# Ethernet.net
KiCad netlist of a schematic drawn in Altium Designer
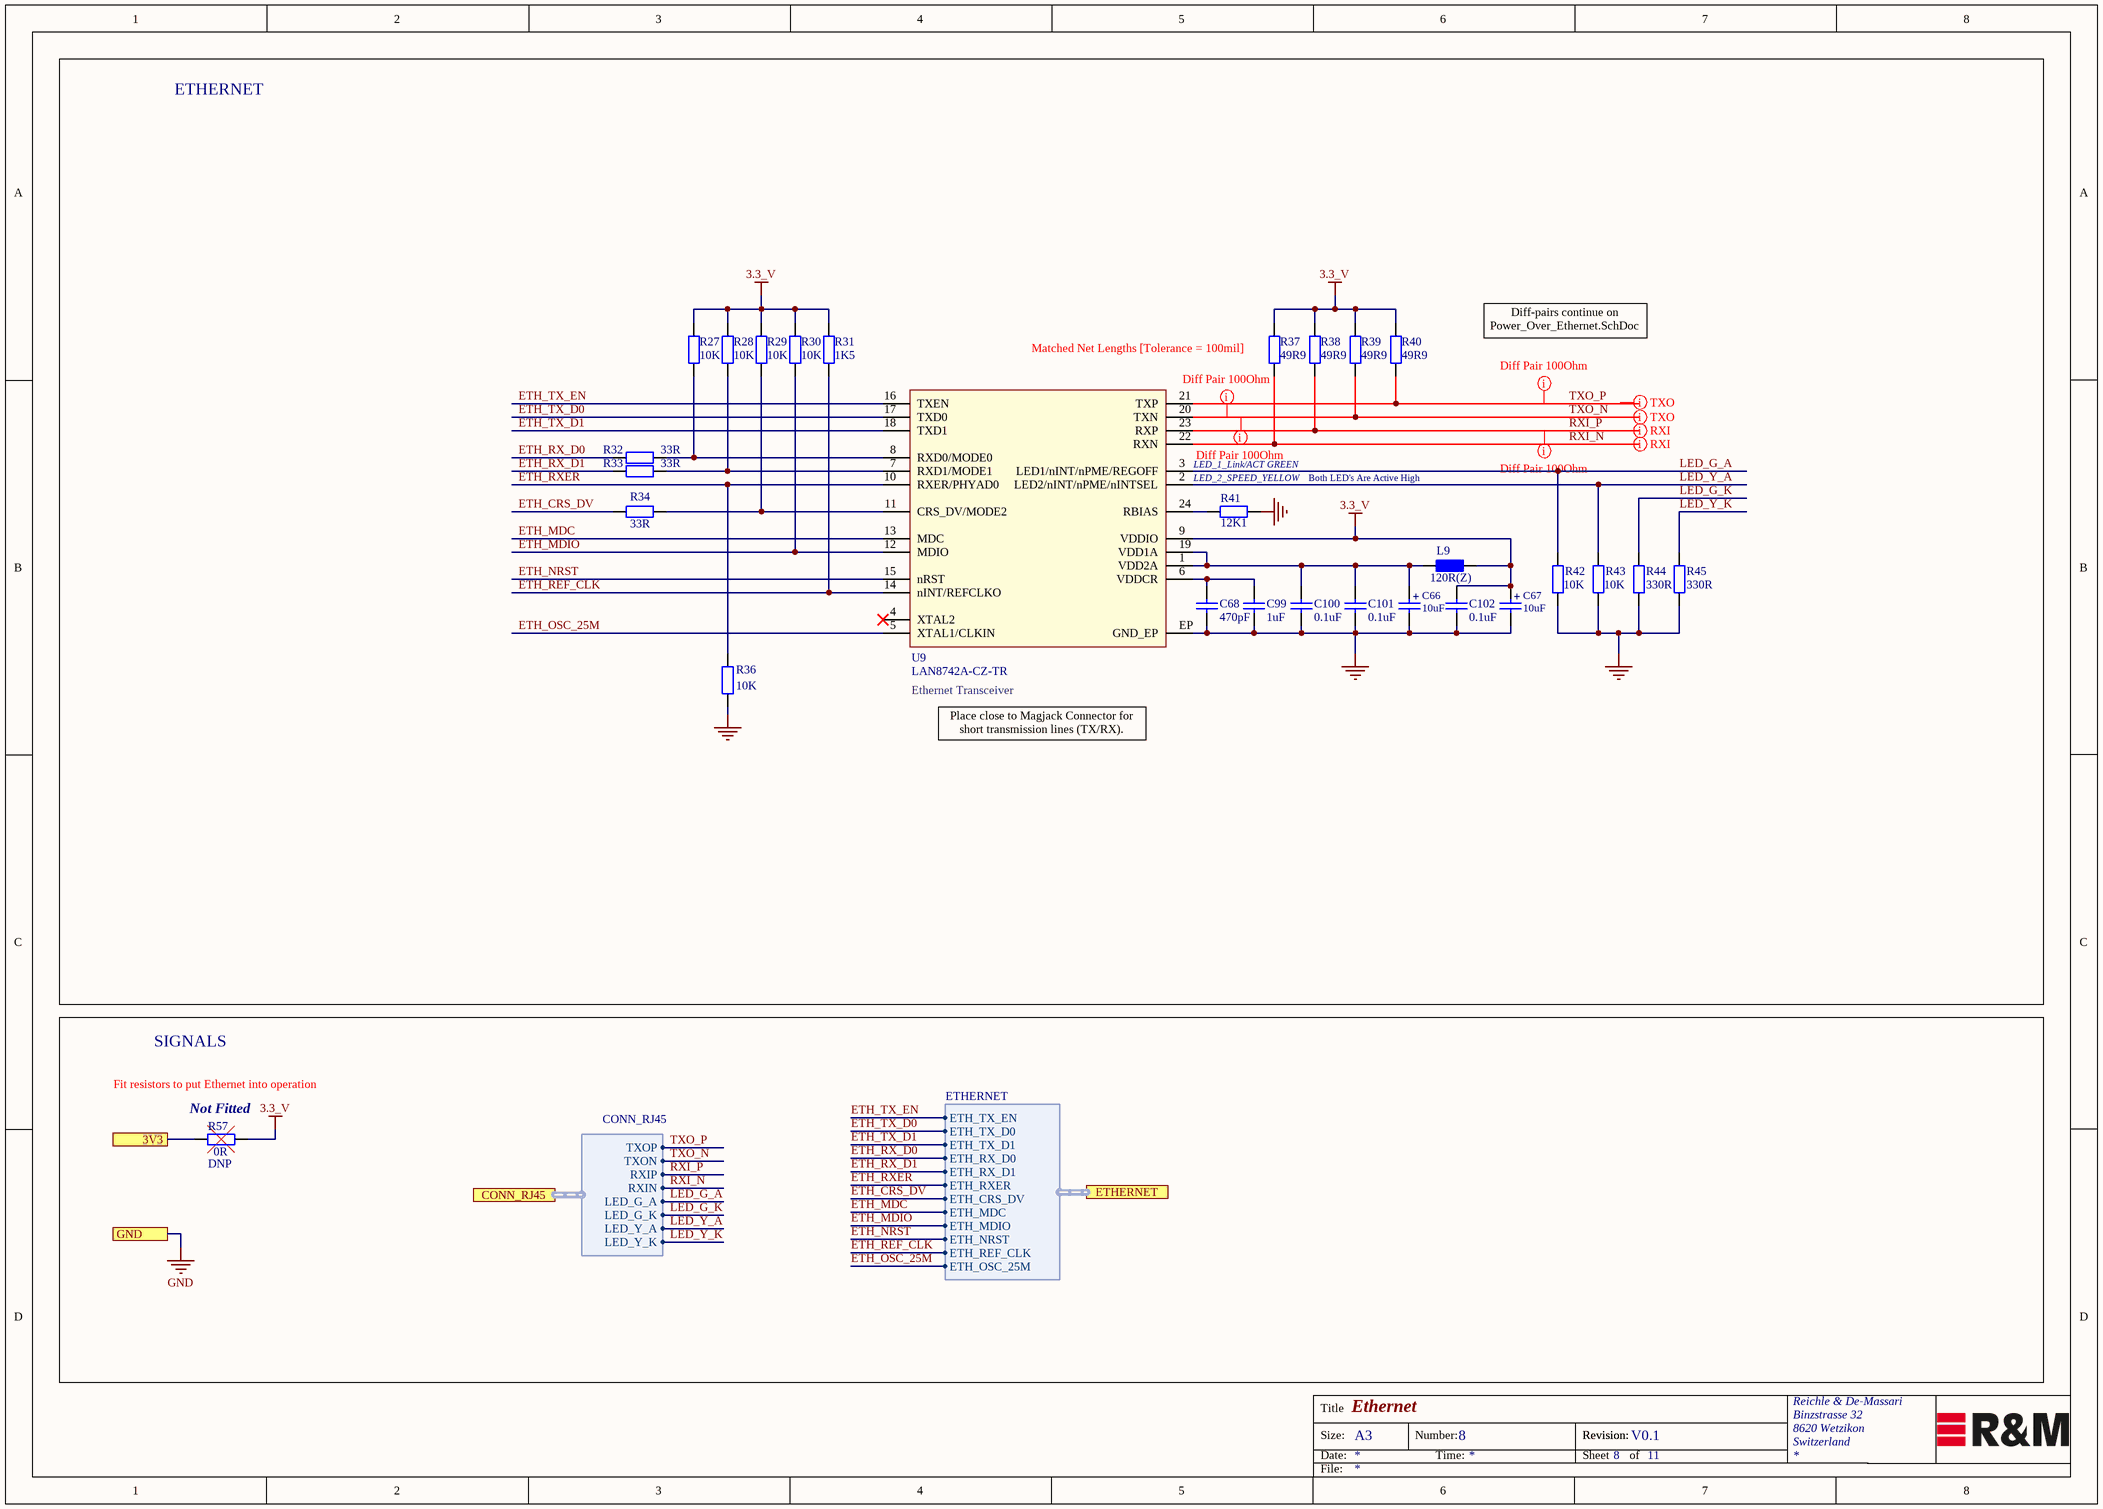
[diagram p0: Ethernet.SchDoc]

(export (version "E")
  (design (tool "Eeschema 10.0.6"))
  (components
    (comp (ref "C66")
      (value "10uF")
      (footprint "293D106X9010A2TE3")
      (description "10µF Molded Tantalum Capacitors 10V 1206 (3216 Metric) 3.4Ohm")
      (fields (field (name "MANUFACTURER") "Vishay Sprague") (field (name "VOLTAGE") "10V"))
      (libsource (lib "RDM_ALT_SCH") (part "Cap_10uF_1206 _10V_Tantal"))
    )
    (comp (ref "C67")
      (value "10uF")
      (footprint "293D106X9010A2TE3")
      (description "10µF Molded Tantalum Capacitors 10V 1206 (3216 Metric) 3.4Ohm")
      (fields (field (name "MANUFACTURER") "Vishay Sprague") (field (name "VOLTAGE") "10V"))
      (libsource (lib "RDM_ALT_SCH") (part "Cap_10uF_1206 _10V_Tantal"))
    )
    (comp (ref "C68")
      (value "470pF")
      (footprint "Ceramic Capacitor 0402 EIA")
      (description "470pF ±10% 16V Ceramic Capacitor X7R 0402 (1005 Metric)")
      (fields (field (name "TOLERANCE") "10%") (field (name "VOLTAGE") "16VDC"))
      (libsource (lib "RDM_ALT_SCH") (part "Cap_470pF_0402_16V"))
    )
    (comp (ref "C99")
      (value "1uF")
      (footprint "Ceramic Capacitor 0402 EIA")
      (description "1µF ±10% 16V Ceramic Capacitor X5R 0603 (1608 Metric)")
      (fields (field (name "TOLERANCE") "10%") (field (name "VOLTAGE") "16VDC"))
      (libsource (lib "RDM_ALT_SCH") (part "Cap_1uF_0603_16V"))
    )
    (comp (ref "C100")
      (value "0.1uF")
      (footprint "Ceramic Capacitor 0402 EIA")
      (description "0.1µF ±10% 16V Ceramic Capacitor X7R 0402 (1005 Metric)")
      (fields (field (name "TOLERANCE") "10%") (field (name "VOLTAGE") "16VDC"))
      (libsource (lib "RDM_ALT_SCH") (part "Cap_0.1uF_0402_16V_10%"))
    )
    (comp (ref "C101")
      (value "0.1uF")
      (footprint "Ceramic Capacitor 0402 EIA")
      (description "0.1µF ±10% 16V Ceramic Capacitor X7R 0402 (1005 Metric)")
      (fields (field (name "TOLERANCE") "10%") (field (name "VOLTAGE") "16VDC"))
      (libsource (lib "RDM_ALT_SCH") (part "Cap_0.1uF_0402_16V_10%"))
    )
    (comp (ref "C102")
      (value "0.1uF")
      (footprint "Ceramic Capacitor 0402 EIA")
      (description "0.1µF ±10% 16V Ceramic Capacitor X7R 0402 (1005 Metric)")
      (fields (field (name "TOLERANCE") "10%") (field (name "VOLTAGE") "16VDC"))
      (libsource (lib "RDM_ALT_SCH") (part "Cap_0.1uF_0402_16V_10%"))
    )
    (comp (ref "L9")
      (value "120R(Z)")
      (footprint "Inductor 0603 EIA")
      (description "120 Ohms @ 100MHz 1 Power Line Ferrite Bead 0603 (1608 Metric) 2A 50mOhm")
      (fields (field (name "MANUFACTURER") "Murata Electronics"))
      (libsource (lib "RDM_ALT_SCH") (part "Ferrit_Bead_0603_BLM18PG121SN1D"))
    )
    (comp (ref "R27")
      (value "10K")
      (footprint "Resistor 0402 EIA")
      (description "SMD 10K ohm 1% 50V General Purpose")
      (fields (field (name "TOLERANCE") "1%") (field (name "POWER") "63mW"))
      (libsource (lib "RDM_ALT_SCH") (part "Res_10K_0402"))
    )
    (comp (ref "R28")
      (value "10K")
      (footprint "Resistor 0402 EIA")
      (description "SMD 10K ohm 1% 50V General Purpose")
      (fields (field (name "TOLERANCE") "1%") (field (name "POWER") "63mW"))
      (libsource (lib "RDM_ALT_SCH") (part "Res_10K_0402"))
    )
    (comp (ref "R29")
      (value "10K")
      (footprint "Resistor 0402 EIA")
      (description "SMD 10K ohm 1% 50V General Purpose")
      (fields (field (name "TOLERANCE") "1%") (field (name "POWER") "63mW"))
      (libsource (lib "RDM_ALT_SCH") (part "Res_10K_0402"))
    )
    (comp (ref "R30")
      (value "10K")
      (footprint "Resistor 0402 EIA")
      (description "SMD 10K ohm 1% 50V General Purpose")
      (fields (field (name "TOLERANCE") "1%") (field (name "POWER") "63mW"))
      (libsource (lib "RDM_ALT_SCH") (part "Res_10K_0402"))
    )
    (comp (ref "R31")
      (value "1K5")
      (footprint "Resistor 0402 EIA")
      (description "1 kOhms ±0.5% 0.063W, 1/16W Chip Resistor 0402 (1005 Metric) Thin Film")
      (fields (field (name "TOLERANCE") "±1%") (field (name "POWER") "1/16W"))
      (libsource (lib "RDM_ALT_SCH") (part "Res_1K5_0402"))
    )
    (comp (ref "R32")
      (value "33R")
      (footprint "Resistor 0402 EIA")
      (description "33 Ohms ±0.1% 0.063W, 1/16W Chip Resistor 0402 (1005 Metric) Thin Film")
      (fields (field (name "MANUFACTURER") "TE Connectivity") (field (name "POWER") "0.063W, 1/16W"))
      (libsource (lib "RDM_ALT_SCH") (part "Res_33R_0402"))
    )
    (comp (ref "R33")
      (value "33R")
      (footprint "Resistor 0402 EIA")
      (description "33 Ohms ±0.1% 0.063W, 1/16W Chip Resistor 0402 (1005 Metric) Thin Film")
      (fields (field (name "MANUFACTURER") "TE Connectivity") (field (name "POWER") "0.063W, 1/16W"))
      (libsource (lib "RDM_ALT_SCH") (part "Res_33R_0402"))
    )
    (comp (ref "R34")
      (value "33R")
      (footprint "Resistor 0402 EIA")
      (description "33 Ohms ±0.1% 0.063W, 1/16W Chip Resistor 0402 (1005 Metric) Thin Film")
      (fields (field (name "MANUFACTURER") "TE Connectivity") (field (name "POWER") "0.063W, 1/16W"))
      (libsource (lib "RDM_ALT_SCH") (part "Res_33R_0402"))
    )
    (comp (ref "R36")
      (value "10K")
      (footprint "Resistor 0402 EIA")
      (description "SMD 10K ohm 1% 50V General Purpose")
      (fields (field (name "TOLERANCE") "1%") (field (name "POWER") "63mW"))
      (libsource (lib "RDM_ALT_SCH") (part "Res_10K_0402"))
    )
    (comp (ref "R37")
      (value "49R9")
      (footprint "Resistor 0402 EIA")
      (description "49.9 Ohms ±0.1% 0.063W, 1/16W Chip Resistor 0402 (1005 Metric) Automotive AEC-Q200 Thin Film")
      (fields (field (name "TOLERANCE") "±0.1%") (field (name "POWER") "0.063W, 1/16W"))
      (libsource (lib "RDM_ALT_SCH") (part "Res_49R9_0402"))
    )
    (comp (ref "R38")
      (value "49R9")
      (footprint "Resistor 0402 EIA")
      (description "49.9 Ohms ±0.1% 0.063W, 1/16W Chip Resistor 0402 (1005 Metric) Automotive AEC-Q200 Thin Film")
      (fields (field (name "TOLERANCE") "±0.1%") (field (name "POWER") "0.063W, 1/16W"))
      (libsource (lib "RDM_ALT_SCH") (part "Res_49R9_0402"))
    )
    (comp (ref "R39")
      (value "49R9")
      (footprint "Resistor 0402 EIA")
      (description "49.9 Ohms ±0.1% 0.063W, 1/16W Chip Resistor 0402 (1005 Metric) Automotive AEC-Q200 Thin Film")
      (fields (field (name "TOLERANCE") "±0.1%") (field (name "POWER") "0.063W, 1/16W"))
      (libsource (lib "RDM_ALT_SCH") (part "Res_49R9_0402"))
    )
    (comp (ref "R40")
      (value "49R9")
      (footprint "Resistor 0402 EIA")
      (description "49.9 Ohms ±0.1% 0.063W, 1/16W Chip Resistor 0402 (1005 Metric) Automotive AEC-Q200 Thin Film")
      (fields (field (name "TOLERANCE") "±0.1%") (field (name "POWER") "0.063W, 1/16W"))
      (libsource (lib "RDM_ALT_SCH") (part "Res_49R9_0402"))
    )
    (comp (ref "R41")
      (value "12K1")
      (footprint "Resistor 0402 EIA")
      (description "12.1 kOhms ±1% 0.063W, 1/16W Chip Resistor 0402 (1005 Metric) Moisture Resistant Thick Film")
      (fields (field (name "TOLERANCE") "±1%") (field (name "POWER") "1/16W"))
      (libsource (lib "RDM_ALT_SCH") (part "Res_12K1_0402"))
    )
    (comp (ref "R42")
      (value "10K")
      (footprint "Resistor 0402 EIA")
      (description "SMD 10K ohm 1% 50V General Purpose")
      (fields (field (name "TOLERANCE") "1%") (field (name "POWER") "63mW"))
      (libsource (lib "RDM_ALT_SCH") (part "Res_10K_0402"))
    )
    (comp (ref "R43")
      (value "10K")
      (footprint "Resistor 0402 EIA")
      (description "SMD 10K ohm 1% 50V General Purpose")
      (fields (field (name "TOLERANCE") "1%") (field (name "POWER") "63mW"))
      (libsource (lib "RDM_ALT_SCH") (part "Res_10K_0402"))
    )
    (comp (ref "R44")
      (value "330R")
      (footprint "Resistor 0402 EIA")
      (description "330 Ohms ±0.1% 0.063W, 1/16W Chip Resistor 0402 (1005 Metric) Automotive AEC-Q200 Thin Film")
      (fields
        (field (name "MANUFACTURER") "Panasonic Electronic Components")
        (field (name "POWER") "0.063W, 1/16W")
      )
      (libsource (lib "RDM_ALT_SCH") (part "Res_330R_0402"))
    )
    (comp (ref "R45")
      (value "330R")
      (footprint "Resistor 0402 EIA")
      (description "330 Ohms ±0.1% 0.063W, 1/16W Chip Resistor 0402 (1005 Metric) Automotive AEC-Q200 Thin Film")
      (fields
        (field (name "MANUFACTURER") "Panasonic Electronic Components")
        (field (name "POWER") "0.063W, 1/16W")
      )
      (libsource (lib "RDM_ALT_SCH") (part "Res_330R_0402"))
    )
    (comp (ref "R57")
      (value "DNP")
      (footprint "Resistor 0805 EIA")
      (description "Resistor: do not populate")
      (fields (field (name "MANUFACTURER") "do not populate"))
      (libsource (lib "RDM_ALT_SCH") (part "Res_DNP_0805"))
    )
    (comp (ref "U9")
      (value "LAN8742A-CZ-TR")
      (footprint "VQFN24-EPAD_4X4")
      (description "10/100M RMII Ethernet transceiver  24-SQFN (4x4)")
      (fields (field (name "VOLTAGE") "1.6V ~ 3.6V") (field (name "MANUFACTURER") "MICROCHIP"))
      (libsource (lib "RDM_ALT_SCH") (part "LAN8742A-CZ-TR"))
    )
  )
  (nets
    (net (code "3") (name "/3V3") (class "Default")
      (node (ref "R57") (pin "1") (pinfunction "1_1") (pintype "passive"))
    )
    (net (code "4") (name "/ETH_CRS_DV") (class "Default")
      (node (ref "R34") (pin "1") (pinfunction "1_1") (pintype "passive"))
    )
    (net (code "5") (name "/ETH_MDC") (class "Default")
      (node (ref "U9") (pin "13") (pinfunction "MDC_13") (pintype "passive"))
    )
    (net (code "6") (name "/ETH_MDIO") (class "Default")
      (node (ref "R30") (pin "2") (pinfunction "2_2") (pintype "passive"))
      (node (ref "U9") (pin "12") (pinfunction "MDIO_12") (pintype "passive"))
    )
    (net (code "7") (name "/ETH_NRST") (class "Default")
      (node (ref "U9") (pin "15") (pinfunction "nRST_15") (pintype "passive"))
    )
    (net (code "8") (name "/ETH_OSC_25M") (class "Default")
      (node (ref "U9") (pin "5") (pinfunction "XTAL1/CLKIN_5") (pintype "passive"))
    )
    (net (code "9") (name "/ETH_REF_CLK") (class "Default")
      (node (ref "R31") (pin "2") (pinfunction "2_2") (pintype "passive"))
      (node (ref "U9") (pin "14") (pinfunction "nINT/REFCLKO_14") (pintype "passive"))
    )
    (net (code "10") (name "/ETH_RXER") (class "Default")
      (node (ref "R36") (pin "1") (pinfunction "1_1") (pintype "passive"))
      (node (ref "U9") (pin "10") (pinfunction "RXER/PHYAD0_10") (pintype "passive"))
    )
    (net (code "11") (name "/ETH_RX_D0") (class "Default")
      (node (ref "R32") (pin "1") (pinfunction "1_1") (pintype "passive"))
    )
    (net (code "12") (name "/ETH_RX_D1") (class "Default")
      (node (ref "R33") (pin "1") (pinfunction "1_1") (pintype "passive"))
    )
    (net (code "13") (name "/ETH_TX_D0") (class "Default")
      (node (ref "U9") (pin "17") (pinfunction "TXD0_17") (pintype "passive"))
    )
    (net (code "14") (name "/ETH_TX_D1") (class "Default")
      (node (ref "U9") (pin "18") (pinfunction "TXD1_18") (pintype "passive"))
    )
    (net (code "15") (name "/ETH_TX_EN") (class "Default")
      (node (ref "U9") (pin "16") (pinfunction "TXEN_16") (pintype "passive"))
    )
    (net (code "16") (name "/LED_G_A") (class "Default")
      (node (ref "R42") (pin "1") (pinfunction "1_1") (pintype "passive"))
      (node (ref "U9") (pin "3") (pinfunction "LED1/nINT/nPME/REGOFF_3") (pintype "passive"))
    )
    (net (code "17") (name "/LED_G_K") (class "Default")
      (node (ref "R44") (pin "1") (pinfunction "1_1") (pintype "passive"))
    )
    (net (code "18") (name "/LED_Y_A") (class "Default")
      (node (ref "R43") (pin "1") (pinfunction "1_1") (pintype "passive"))
      (node (ref "U9") (pin "2") (pinfunction "LED2/nINT/nPME/nINTSEL_2") (pintype "passive"))
    )
    (net (code "19") (name "/LED_Y_K") (class "Default")
      (node (ref "R45") (pin "1") (pinfunction "1_1") (pintype "passive"))
    )
    (net (code "20") (name "/RXI_N") (class "Default")
      (node (ref "R37") (pin "2") (pinfunction "2_2") (pintype "passive"))
      (node (ref "U9") (pin "22") (pinfunction "RXN_22") (pintype "passive"))
    )
    (net (code "21") (name "/RXI_P") (class "Default")
      (node (ref "R38") (pin "2") (pinfunction "2_2") (pintype "passive"))
      (node (ref "U9") (pin "23") (pinfunction "RXP_23") (pintype "passive"))
    )
    (net (code "22") (name "/TXO_N") (class "Default")
      (node (ref "R39") (pin "2") (pinfunction "2_2") (pintype "passive"))
      (node (ref "U9") (pin "20") (pinfunction "TXN_20") (pintype "passive"))
    )
    (net (code "23") (name "/TXO_P") (class "Default")
      (node (ref "R40") (pin "2") (pinfunction "2_2") (pintype "passive"))
      (node (ref "U9") (pin "21") (pinfunction "TXP_21") (pintype "passive"))
    )
    (net (code "26") (name "3.3_V") (class "Default")
      (node (ref "C102") (pin "2") (pinfunction "2_2") (pintype "passive"))
      (node (ref "C67") (pin "1") (pinfunction "Pos_1") (pintype "passive"))
      (node (ref "L9") (pin "2") (pinfunction "2_2") (pintype "passive"))
      (node (ref "R27") (pin "1") (pinfunction "1_1") (pintype "passive"))
      (node (ref "R28") (pin "1") (pinfunction "1_1") (pintype "passive"))
      (node (ref "R29") (pin "1") (pinfunction "1_1") (pintype "passive"))
      (node (ref "R30") (pin "1") (pinfunction "1_1") (pintype "passive"))
      (node (ref "R31") (pin "1") (pinfunction "1_1") (pintype "passive"))
      (node (ref "R37") (pin "1") (pinfunction "1_1") (pintype "passive"))
      (node (ref "R38") (pin "1") (pinfunction "1_1") (pintype "passive"))
      (node (ref "R39") (pin "1") (pinfunction "1_1") (pintype "passive"))
      (node (ref "R40") (pin "1") (pinfunction "1_1") (pintype "passive"))
      (node (ref "R57") (pin "2") (pinfunction "2_2") (pintype "passive"))
      (node (ref "U9") (pin "9") (pinfunction "VDDIO_9") (pintype "passive"))
    )
    (net (code "27") (name "GND") (class "Default")
      (node (ref "C100") (pin "1") (pinfunction "1_1") (pintype "passive"))
      (node (ref "C101") (pin "1") (pinfunction "1_1") (pintype "passive"))
      (node (ref "C102") (pin "1") (pinfunction "1_1") (pintype "passive"))
      (node (ref "C66") (pin "2") (pinfunction "Neg_2") (pintype "passive"))
      (node (ref "C67") (pin "2") (pinfunction "Neg_2") (pintype "passive"))
      (node (ref "C68") (pin "1") (pinfunction "1_1") (pintype "passive"))
      (node (ref "C99") (pin "1") (pinfunction "1_1") (pintype "passive"))
      (node (ref "R36") (pin "2") (pinfunction "2_2") (pintype "passive"))
      (node (ref "R41") (pin "2") (pinfunction "2_2") (pintype "passive"))
      (node (ref "R42") (pin "2") (pinfunction "2_2") (pintype "passive"))
      (node (ref "R43") (pin "2") (pinfunction "2_2") (pintype "passive"))
      (node (ref "R44") (pin "2") (pinfunction "2_2") (pintype "passive"))
      (node (ref "R45") (pin "2") (pinfunction "2_2") (pintype "passive"))
      (node (ref "U9") (pin "EP") (pinfunction "GND_EP_EP") (pintype "passive"))
    )
    (net (code "28") (name "Net-(C66-Pos)") (class "Default")
      (node (ref "C100") (pin "2") (pinfunction "2_2") (pintype "passive"))
      (node (ref "C101") (pin "2") (pinfunction "2_2") (pintype "passive"))
      (node (ref "C66") (pin "1") (pinfunction "Pos_1") (pintype "passive"))
      (node (ref "L9") (pin "1") (pinfunction "1_1") (pintype "passive"))
      (node (ref "U9") (pin "1") (pinfunction "VDD2A_1") (pintype "passive"))
      (node (ref "U9") (pin "19") (pinfunction "VDD1A_19") (pintype "passive"))
    )
    (net (code "29") (name "Net-(U9-CRS_DV{slash}MODE2)") (class "Default")
      (node (ref "R29") (pin "2") (pinfunction "2_2") (pintype "passive"))
      (node (ref "R34") (pin "2") (pinfunction "2_2") (pintype "passive"))
      (node (ref "U9") (pin "11") (pinfunction "CRS_DV/MODE2_11") (pintype "passive"))
    )
    (net (code "30") (name "Net-(U9-RBIAS)") (class "Default")
      (node (ref "R41") (pin "1") (pinfunction "1_1") (pintype "passive"))
      (node (ref "U9") (pin "24") (pinfunction "RBIAS_24") (pintype "passive"))
    )
    (net (code "31") (name "Net-(U9-RXD0{slash}MODE0)") (class "Default")
      (node (ref "R27") (pin "2") (pinfunction "2_2") (pintype "passive"))
      (node (ref "R32") (pin "2") (pinfunction "2_2") (pintype "passive"))
      (node (ref "U9") (pin "8") (pinfunction "RXD0/MODE0_8") (pintype "passive"))
    )
    (net (code "32") (name "Net-(U9-RXD1{slash}MODE1)") (class "Default")
      (node (ref "R28") (pin "2") (pinfunction "2_2") (pintype "passive"))
      (node (ref "R33") (pin "2") (pinfunction "2_2") (pintype "passive"))
      (node (ref "U9") (pin "7") (pinfunction "RXD1/MODE1_7") (pintype "passive"))
    )
    (net (code "33") (name "Net-(U9-VDDCR)") (class "Default")
      (node (ref "C68") (pin "2") (pinfunction "2_2") (pintype "passive"))
      (node (ref "C99") (pin "2") (pinfunction "2_2") (pintype "passive"))
      (node (ref "U9") (pin "6") (pinfunction "VDDCR_6") (pintype "passive"))
    )
    (net (code "34") (name "unconnected-(U9-XTAL2-Pad4)") (class "Default")
      (node (ref "U9") (pin "4") (pinfunction "XTAL2_4") (pintype "passive+no_connect"))
    )
  )
)
